# shield_layer2.net
KiCad netlist of a schematic drawn in EAGLE
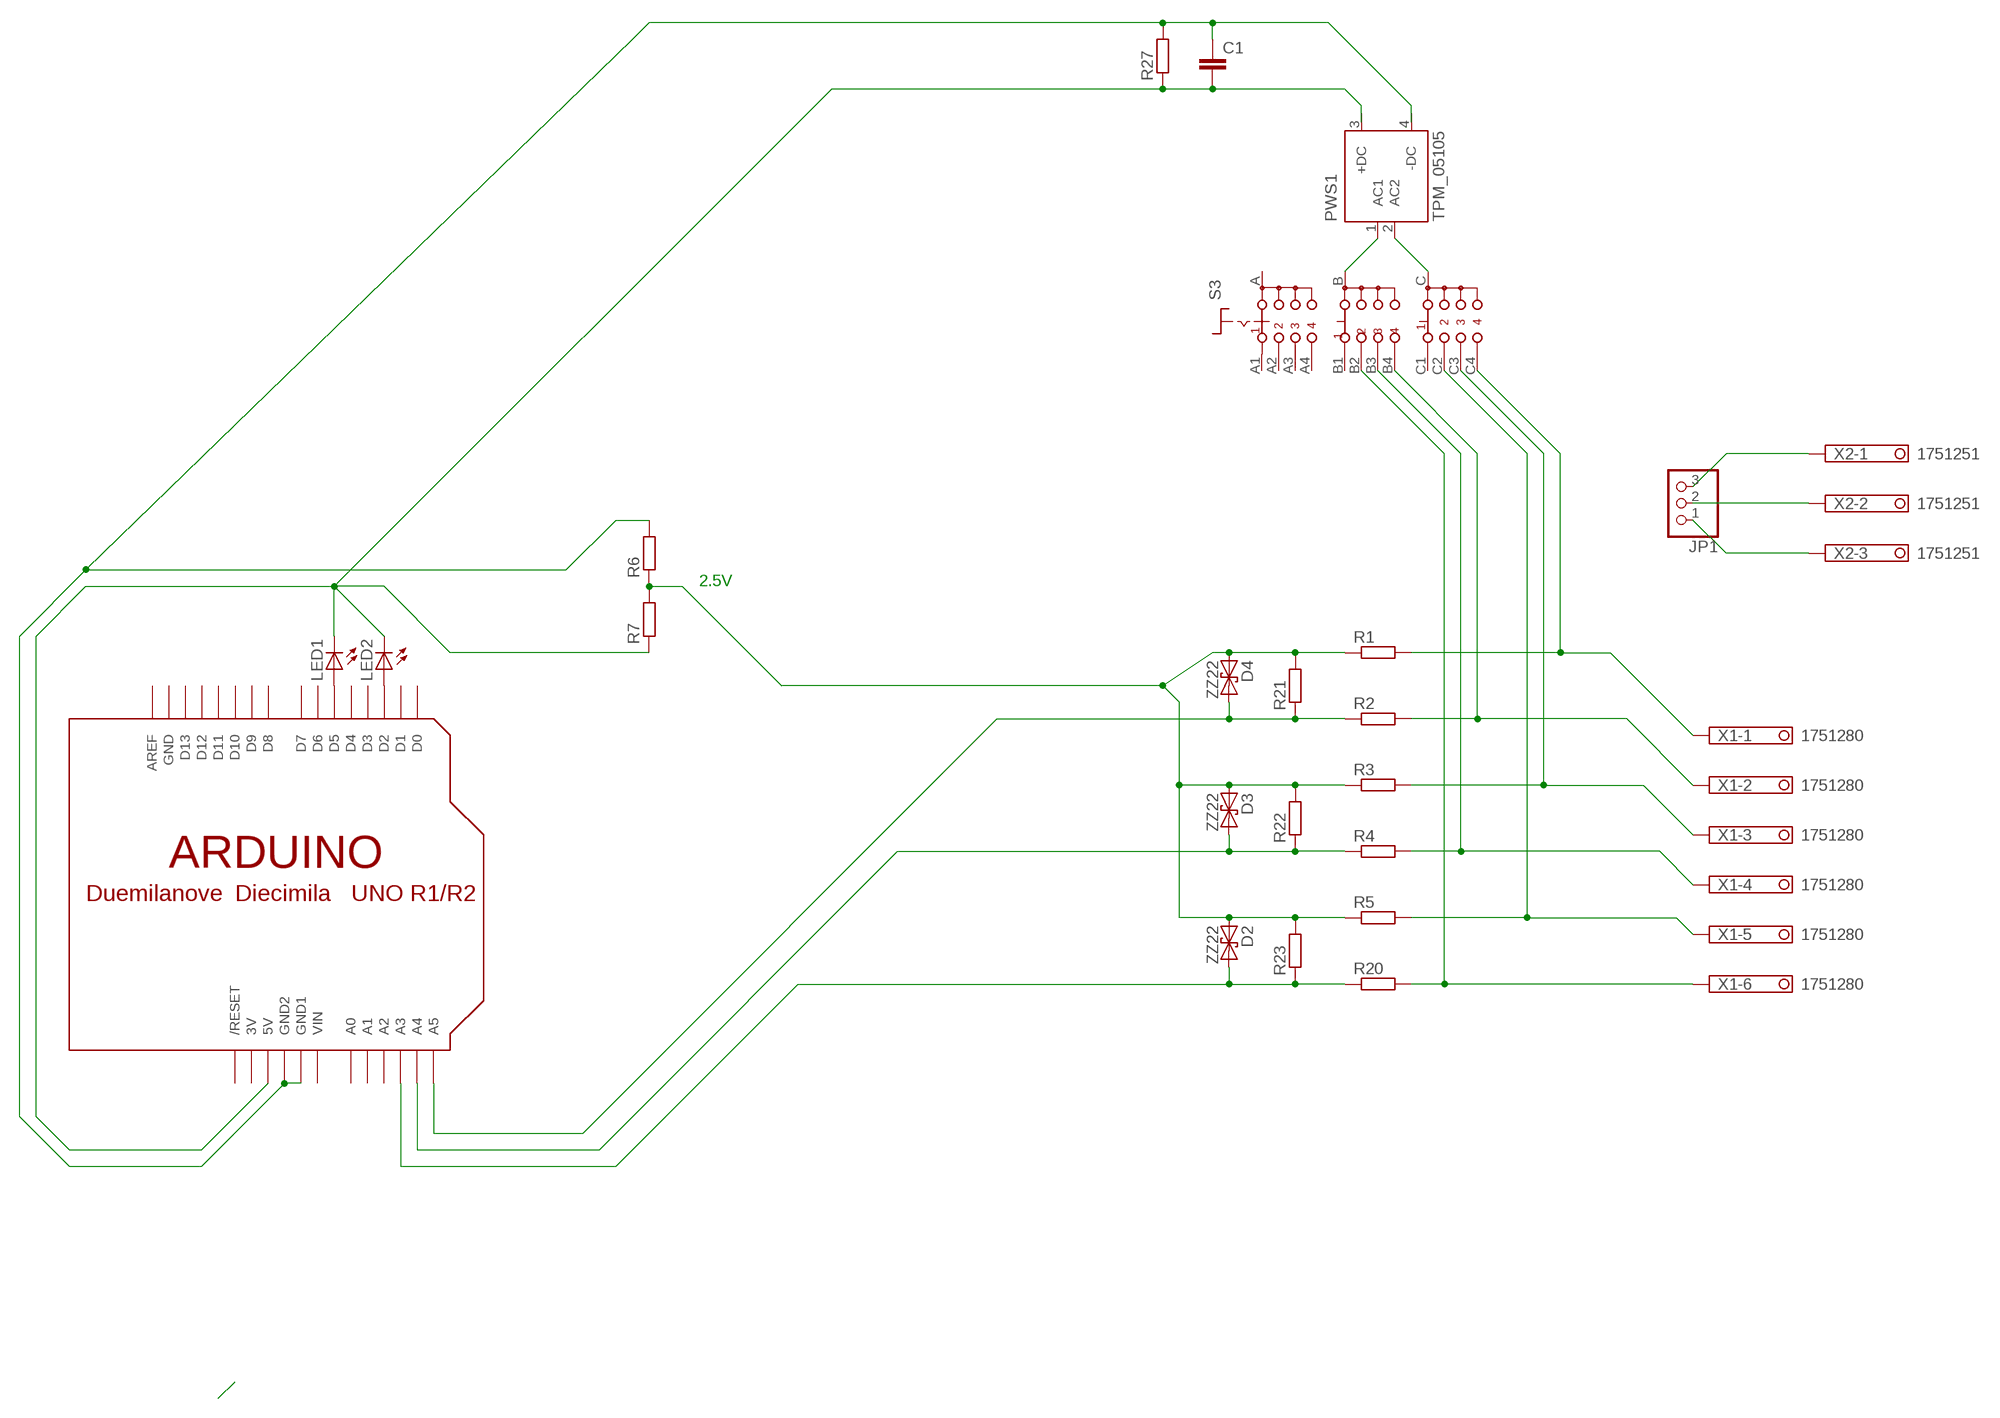
[diagram p0: schematic, sheet 1]

(export (version "E")
  (design (tool "Eeschema 10.0.6"))
  (components
    (comp (ref "C1")
      (value "C-EU050-045X075")
      (footprint "eagle-import:C050-045X075")
      (libsource (lib "eagle-import") (part "C-EU050-045X075"))
    )
    (comp (ref "D2")
      (value "ZZ22")
      (footprint "eagle-import:P2-15")
      (libsource (lib "eagle-import") (part "ZZ22"))
    )
    (comp (ref "D3")
      (value "ZZ22")
      (footprint "eagle-import:P2-15")
      (libsource (lib "eagle-import") (part "ZZ22"))
    )
    (comp (ref "D4")
      (value "ZZ22")
      (footprint "eagle-import:P2-15")
      (libsource (lib "eagle-import") (part "ZZ22"))
    )
    (comp (ref "JP1")
      (value "PINHD-1X3CB")
      (footprint "eagle-import:1X03-CLEANBIG")
      (libsource (lib "eagle-import") (part "PINHD-1X3CB"))
    )
    (comp (ref "LED1")
      (value "LED5MM")
      (footprint "eagle-import:LED5MM")
      (libsource (lib "eagle-import") (part "LED5MM"))
    )
    (comp (ref "LED2")
      (value "LED5MM")
      (footprint "eagle-import:LED5MM")
      (libsource (lib "eagle-import") (part "LED5MM"))
    )
    (comp (ref "PWS1")
      (value "TPM_05105")
      (footprint "eagle-import:05105")
      (libsource (lib "eagle-import") (part "TPM_05105"))
    )
    (comp (ref "R1")
      (value "R-EU_0617/22")
      (footprint "eagle-import:0617_22")
      (libsource (lib "eagle-import") (part "R-EU_0617/22"))
    )
    (comp (ref "R2")
      (value "R-EU_0617/22")
      (footprint "eagle-import:0617_22")
      (libsource (lib "eagle-import") (part "R-EU_0617/22"))
    )
    (comp (ref "R3")
      (value "R-EU_0617/22")
      (footprint "eagle-import:0617_22")
      (libsource (lib "eagle-import") (part "R-EU_0617/22"))
    )
    (comp (ref "R4")
      (value "R-EU_0617/22")
      (footprint "eagle-import:0617_22")
      (libsource (lib "eagle-import") (part "R-EU_0617/22"))
    )
    (comp (ref "R5")
      (value "R-EU_0617/22")
      (footprint "eagle-import:0617_22")
      (libsource (lib "eagle-import") (part "R-EU_0617/22"))
    )
    (comp (ref "R6")
      (value "R-EU_0207/10")
      (footprint "eagle-import:0207_10")
      (libsource (lib "eagle-import") (part "R-EU_0207/10"))
    )
    (comp (ref "R7")
      (value "R-EU_0207/10")
      (footprint "eagle-import:0207_10")
      (libsource (lib "eagle-import") (part "R-EU_0207/10"))
    )
    (comp (ref "R20")
      (value "R-EU_0617/22")
      (footprint "eagle-import:0617_22")
      (libsource (lib "eagle-import") (part "R-EU_0617/22"))
    )
    (comp (ref "R21")
      (value "R-EU_0207/10")
      (footprint "eagle-import:0207_10")
      (libsource (lib "eagle-import") (part "R-EU_0207/10"))
    )
    (comp (ref "R22")
      (value "R-EU_0207/10")
      (footprint "eagle-import:0207_10")
      (libsource (lib "eagle-import") (part "R-EU_0207/10"))
    )
    (comp (ref "R23")
      (value "R-EU_0207/10")
      (footprint "eagle-import:0207_10")
      (libsource (lib "eagle-import") (part "R-EU_0207/10"))
    )
    (comp (ref "R27")
      (value "R-EU_0207/10")
      (footprint "eagle-import:0207_10")
      (libsource (lib "eagle-import") (part "R-EU_0207/10"))
    )
    (comp (ref "S3")
      (value "CK103X04")
      (footprint "eagle-import:CK103X04")
      (libsource (lib "eagle-import") (part "CK103X04"))
    )
    (comp (ref "U$1")
      (value "ARDUINOUNO")
      (footprint "eagle-import:ARDUINO")
      (libsource (lib "eagle-import") (part "ARDUINOUNO"))
    )
    (comp (ref "X1")
      (value "1751280")
      (footprint "eagle-import:1751280")
      (libsource (lib "eagle-import") (part "1751280"))
    )
    (comp (ref "X2")
      (value "1751251")
      (footprint "eagle-import:1751251")
      (libsource (lib "eagle-import") (part "1751251"))
    )
  )
  (nets
    (net (code "1") (name "/3V") (class "Default")
      (node (ref "U$1") (pin "3V") (pinfunction "3V_3V") (pintype "power_in"))
    )
    (net (code "2") (name "/GND") (class "Default")
      (node (ref "U$1") (pin "GND") (pinfunction "GND_GND") (pintype "power_in"))
    )
    (net (code "3") (name "/VIN") (class "Default")
      (node (ref "U$1") (pin "VIN") (pinfunction "VIN_VIN") (pintype "power_in"))
    )
    (net (code "4") (name "Net-(C1-Pad1)") (class "Default")
      (node (ref "C1") (pin "1") (pinfunction "1_1") (pintype "passive"))
      (node (ref "R27") (pin "2") (pinfunction "2_2") (pintype "passive"))
      (node (ref "R6") (pin "2") (pinfunction "2_2") (pintype "passive"))
      (node (ref "U$1") (pin "GND1") (pinfunction "GND1_GND1") (pintype "power_in"))
      (node (ref "U$1") (pin "GND2") (pinfunction "GND2_GND2") (pintype "power_in"))
    )
    (net (code "5") (name "Net-(D2-1)") (class "Default")
      (node (ref "D2") (pin "A") (pinfunction "1_A") (pintype "passive"))
      (node (ref "D3") (pin "A") (pinfunction "1_A") (pintype "passive"))
      (node (ref "D4") (pin "A") (pinfunction "1_A") (pintype "passive"))
      (node (ref "R1") (pin "1") (pinfunction "1_1") (pintype "passive"))
      (node (ref "R21") (pin "2") (pinfunction "2_2") (pintype "passive"))
      (node (ref "R22") (pin "2") (pinfunction "2_2") (pintype "passive"))
      (node (ref "R23") (pin "2") (pinfunction "2_2") (pintype "passive"))
      (node (ref "R3") (pin "1") (pinfunction "1_1") (pintype "passive"))
      (node (ref "R5") (pin "1") (pinfunction "1_1") (pintype "passive"))
      (node (ref "R6") (pin "1") (pinfunction "1_1") (pintype "passive"))
      (node (ref "R7") (pin "2") (pinfunction "2_2") (pintype "passive"))
    )
    (net (code "6") (name "Net-(D2-2)") (class "Default")
      (node (ref "D2") (pin "C") (pinfunction "2_C") (pintype "passive"))
      (node (ref "R20") (pin "1") (pinfunction "1_1") (pintype "passive"))
      (node (ref "R23") (pin "1") (pinfunction "1_1") (pintype "passive"))
      (node (ref "U$1") (pin "A3") (pinfunction "A3_A3") (pintype "bidirectional"))
    )
    (net (code "7") (name "Net-(D3-2)") (class "Default")
      (node (ref "D3") (pin "C") (pinfunction "2_C") (pintype "passive"))
      (node (ref "R22") (pin "1") (pinfunction "1_1") (pintype "passive"))
      (node (ref "R4") (pin "1") (pinfunction "1_1") (pintype "passive"))
      (node (ref "U$1") (pin "A4") (pinfunction "A4_A4") (pintype "bidirectional"))
    )
    (net (code "8") (name "Net-(D4-2)") (class "Default")
      (node (ref "D4") (pin "C") (pinfunction "2_C") (pintype "passive"))
      (node (ref "R2") (pin "1") (pinfunction "1_1") (pintype "passive"))
      (node (ref "R21") (pin "1") (pinfunction "1_1") (pintype "passive"))
      (node (ref "U$1") (pin "A5") (pinfunction "A5_A5") (pintype "bidirectional"))
    )
    (net (code "9") (name "Net-(LED1-C)") (class "Default")
      (node (ref "C1") (pin "2") (pinfunction "2_2") (pintype "passive"))
      (node (ref "LED1") (pin "K") (pinfunction "C_K") (pintype "passive"))
      (node (ref "LED2") (pin "K") (pinfunction "C_K") (pintype "passive"))
      (node (ref "R27") (pin "1") (pinfunction "1_1") (pintype "passive"))
      (node (ref "R7") (pin "1") (pinfunction "1_1") (pintype "passive"))
      (node (ref "U$1") (pin "5V") (pinfunction "5V_5V") (pintype "power_in"))
    )
    (net (code "10") (name "Net-(LED1-PadA)") (class "Default")
      (node (ref "LED1") (pin "A") (pinfunction "A_A") (pintype "passive"))
      (node (ref "U$1") (pin "D5") (pinfunction "D5_D5") (pintype "bidirectional"))
    )
    (net (code "11") (name "Net-(LED2-PadA)") (class "Default")
      (node (ref "LED2") (pin "A") (pinfunction "A_A") (pintype "passive"))
      (node (ref "U$1") (pin "D2") (pinfunction "D2_D2") (pintype "bidirectional"))
    )
    (net (code "12") (name "Net-(PWS1-AC1)") (class "Default")
      (node (ref "PWS1") (pin "1") (pinfunction "AC1_1") (pintype "input"))
      (node (ref "S3") (pin "B") (pinfunction "B_B") (pintype "passive"))
    )
    (net (code "13") (name "Net-(PWS1-AC2)") (class "Default")
      (node (ref "PWS1") (pin "2") (pinfunction "AC2_2") (pintype "input"))
      (node (ref "S3") (pin "C") (pinfunction "C_C") (pintype "passive"))
    )
    (net (code "14") (name "Net-(X1A-K)") (class "Default")
      (node (ref "R1") (pin "2") (pinfunction "2_2") (pintype "passive"))
      (node (ref "S3") (pin "C4") (pinfunction "C4_C4") (pintype "passive"))
      (node (ref "X1") (pin "1") (pinfunction "K_1") (pintype "passive"))
    )
    (net (code "15") (name "Net-(X1B-K)") (class "Default")
      (node (ref "R2") (pin "2") (pinfunction "2_2") (pintype "passive"))
      (node (ref "S3") (pin "B4") (pinfunction "B4_B4") (pintype "passive"))
      (node (ref "X1") (pin "2") (pinfunction "K_2") (pintype "passive"))
    )
    (net (code "16") (name "Net-(X1C-K)") (class "Default")
      (node (ref "R3") (pin "2") (pinfunction "2_2") (pintype "passive"))
      (node (ref "S3") (pin "C3") (pinfunction "C3_C3") (pintype "passive"))
      (node (ref "X1") (pin "3") (pinfunction "K_3") (pintype "passive"))
    )
    (net (code "17") (name "Net-(X1D-K)") (class "Default")
      (node (ref "R4") (pin "2") (pinfunction "2_2") (pintype "passive"))
      (node (ref "S3") (pin "B3") (pinfunction "B3_B3") (pintype "passive"))
      (node (ref "X1") (pin "4") (pinfunction "K_4") (pintype "passive"))
    )
    (net (code "18") (name "Net-(X1E-K)") (class "Default")
      (node (ref "R5") (pin "2") (pinfunction "2_2") (pintype "passive"))
      (node (ref "S3") (pin "C2") (pinfunction "C2_C2") (pintype "passive"))
      (node (ref "X1") (pin "5") (pinfunction "K_5") (pintype "passive"))
    )
    (net (code "19") (name "Net-(X1F-K)") (class "Default")
      (node (ref "R20") (pin "2") (pinfunction "2_2") (pintype "passive"))
      (node (ref "S3") (pin "B2") (pinfunction "B2_B2") (pintype "passive"))
      (node (ref "X1") (pin "6") (pinfunction "K_6") (pintype "passive"))
    )
    (net (code "20") (name "Net-(X2A-K)") (class "Default")
      (node (ref "JP1") (pin "3") (pinfunction "3_3") (pintype "passive"))
      (node (ref "X2") (pin "1") (pinfunction "K_1") (pintype "passive"))
    )
    (net (code "21") (name "Net-(X2B-K)") (class "Default")
      (node (ref "JP1") (pin "2") (pinfunction "2_2") (pintype "passive"))
      (node (ref "X2") (pin "2") (pinfunction "K_2") (pintype "passive"))
    )
    (net (code "22") (name "Net-(X2C-K)") (class "Default")
      (node (ref "JP1") (pin "1") (pinfunction "1_1") (pintype "passive"))
      (node (ref "X2") (pin "3") (pinfunction "K_3") (pintype "passive"))
    )
    (net (code "23") (name "unconnected-(PWS1-+DC-Pad3)") (class "Default")
      (node (ref "PWS1") (pin "3") (pinfunction "+DC_3") (pintype "passive"))
    )
    (net (code "24") (name "unconnected-(PWS1--DC-Pad4)") (class "Default")
      (node (ref "PWS1") (pin "4") (pinfunction "-DC_4") (pintype "passive"))
    )
    (net (code "25") (name "unconnected-(S3-PadA)") (class "Default")
      (node (ref "S3") (pin "A") (pinfunction "A_A") (pintype "passive"))
    )
    (net (code "26") (name "unconnected-(S3-PadA1)") (class "Default")
      (node (ref "S3") (pin "A1") (pinfunction "A1_A1") (pintype "passive"))
    )
    (net (code "27") (name "unconnected-(S3-PadA2)") (class "Default")
      (node (ref "S3") (pin "A2") (pinfunction "A2_A2") (pintype "passive"))
    )
    (net (code "28") (name "unconnected-(S3-PadA3)") (class "Default")
      (node (ref "S3") (pin "A3") (pinfunction "A3_A3") (pintype "passive"))
    )
    (net (code "29") (name "unconnected-(S3-PadA4)") (class "Default")
      (node (ref "S3") (pin "A4") (pinfunction "A4_A4") (pintype "passive"))
    )
    (net (code "30") (name "unconnected-(S3-PadB1)") (class "Default")
      (node (ref "S3") (pin "B1") (pinfunction "B1_B1") (pintype "passive"))
    )
    (net (code "31") (name "unconnected-(S3-PadC1)") (class "Default")
      (node (ref "S3") (pin "C1") (pinfunction "C1_C1") (pintype "passive"))
    )
    (net (code "32") (name "unconnected-(U$1-PadA0)") (class "Default")
      (node (ref "U$1") (pin "A0") (pinfunction "A0_A0") (pintype "bidirectional"))
    )
    (net (code "33") (name "unconnected-(U$1-PadA1)") (class "Default")
      (node (ref "U$1") (pin "A1") (pinfunction "A1_A1") (pintype "bidirectional"))
    )
    (net (code "34") (name "unconnected-(U$1-PadA2)") (class "Default")
      (node (ref "U$1") (pin "A2") (pinfunction "A2_A2") (pintype "bidirectional"))
    )
    (net (code "35") (name "unconnected-(U$1-PadAREF)") (class "Default")
      (node (ref "U$1") (pin "AREF") (pinfunction "AREF_AREF") (pintype "bidirectional"))
    )
    (net (code "36") (name "unconnected-(U$1-PadD0)") (class "Default")
      (node (ref "U$1") (pin "D0") (pinfunction "D0_D0") (pintype "bidirectional"))
    )
    (net (code "37") (name "unconnected-(U$1-PadD1)") (class "Default")
      (node (ref "U$1") (pin "D1") (pinfunction "D1_D1") (pintype "bidirectional"))
    )
    (net (code "38") (name "unconnected-(U$1-PadD3)") (class "Default")
      (node (ref "U$1") (pin "D3") (pinfunction "D3_D3") (pintype "bidirectional"))
    )
    (net (code "39") (name "unconnected-(U$1-PadD4)") (class "Default")
      (node (ref "U$1") (pin "D4") (pinfunction "D4_D4") (pintype "bidirectional"))
    )
    (net (code "40") (name "unconnected-(U$1-PadD6)") (class "Default")
      (node (ref "U$1") (pin "D6") (pinfunction "D6_D6") (pintype "bidirectional"))
    )
    (net (code "41") (name "unconnected-(U$1-PadD7)") (class "Default")
      (node (ref "U$1") (pin "D7") (pinfunction "D7_D7") (pintype "bidirectional"))
    )
    (net (code "42") (name "unconnected-(U$1-PadD8)") (class "Default")
      (node (ref "U$1") (pin "D8") (pinfunction "D8_D8") (pintype "bidirectional"))
    )
    (net (code "43") (name "unconnected-(U$1-PadD9)") (class "Default")
      (node (ref "U$1") (pin "D9") (pinfunction "D9_D9") (pintype "bidirectional"))
    )
    (net (code "44") (name "unconnected-(U$1-PadD10)") (class "Default")
      (node (ref "U$1") (pin "D10") (pinfunction "D10_D10") (pintype "bidirectional"))
    )
    (net (code "45") (name "unconnected-(U$1-PadD11)") (class "Default")
      (node (ref "U$1") (pin "D11") (pinfunction "D11_D11") (pintype "bidirectional"))
    )
    (net (code "46") (name "unconnected-(U$1-PadD12)") (class "Default")
      (node (ref "U$1") (pin "D12") (pinfunction "D12_D12") (pintype "bidirectional"))
    )
    (net (code "47") (name "unconnected-(U$1-PadD13)") (class "Default")
      (node (ref "U$1") (pin "D13") (pinfunction "D13_D13") (pintype "bidirectional"))
    )
    (net (code "48") (name "unconnected-(U$1-{slash}RESET-PadRESET)") (class "Default")
      (node (ref "U$1") (pin "RESET") (pinfunction "/RESET_RESET") (pintype "bidirectional"))
    )
  )
)
